# ADC2.net
KiCad netlist of a schematic drawn in Altium Designer
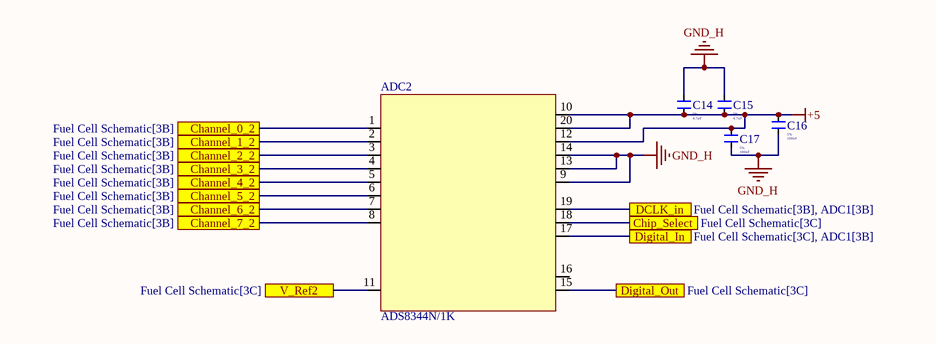
[diagram p0: ADC2.SchDoc]

(export (version "E")
  (design (tool "Eeschema 10.0.6"))
  (components
    (comp (ref "ADC2")
      (value "ADS8344N/1K")
      (footprint "ADS8344")
      (description "IC ADC 16BIT SAR 20SSOP")
      (fields (field (name "MANUFACTURER") "Texas Instruments"))
      (libsource (lib "Schlib1") (part "ADS8344N/1K"))
    )
    (comp (ref "C14")
      (value "~")
      (footprint "Capacitor_Kemet_0805")
      (description "CAP CER 4.7UF 16V X7R 0805")
      (fields
        (field (name "MANUFACTURER") "KEMET")
        (field (name "MANUFACTURER PART NUMBER") "C0805C475J4RACAUTO")
        (field (name "TOLERANCE") "5%")
        (field (name "CAPACITANCE") "4.7uF")
      )
      (libsource (lib "Schlib1") (part "C0805C475J4RACAUTO"))
    )
    (comp (ref "C15")
      (value "~")
      (footprint "Capacitor_Kemet_0805")
      (description "CAP CER 4.7UF 16V X7R 0805")
      (fields
        (field (name "MANUFACTURER") "KEMET")
        (field (name "MANUFACTURER PART NUMBER") "C0805C475J4RACAUTO")
        (field (name "TOLERANCE") "5%")
        (field (name "CAPACITANCE") "4.7uF")
      )
      (libsource (lib "Schlib1") (part "C0805C475J4RACAUTO"))
    )
    (comp (ref "C16")
      (value "~")
      (footprint "Capacitor_Kemet_0805")
      (description "Cap Ceramic 0.1uF 16V X7R 5% SMD 0805 125°C Plastic T/R")
      (fields
        (field (name "MANUFACTURER") "KEMET")
        (field (name "MANUFACTURER PART NUMBER") "C0805C104J4RACTU")
        (field (name "DISSIPATION FACTOR") "5%")
        (field (name "CAPACITANCE") "100nF")
      )
      (libsource (lib "Schlib1") (part "C0805C104J4RACTU"))
    )
    (comp (ref "C17")
      (value "~")
      (footprint "Capacitor_Kemet_0805")
      (description "Cap Ceramic 0.1uF 16V X7R 5% SMD 0805 125°C Plastic T/R")
      (fields
        (field (name "MANUFACTURER") "KEMET")
        (field (name "MANUFACTURER PART NUMBER") "C0805C104J4RACTU")
        (field (name "DISSIPATION FACTOR") "5%")
        (field (name "CAPACITANCE") "100nF")
      )
      (libsource (lib "Schlib1") (part "C0805C104J4RACTU"))
    )
  )
  (nets
    (net (code "1") (name "+5") (class "Default")
      (node (ref "ADC2") (pin "10") (pinfunction "Shutdown_10") (pintype "passive"))
      (node (ref "ADC2") (pin "12") (pinfunction "+VCC_12") (pintype "passive"))
      (node (ref "ADC2") (pin "20") (pinfunction "+VCC_20") (pintype "passive"))
      (node (ref "C14") (pin "1") (pinfunction "1_1") (pintype "passive"))
      (node (ref "C15") (pin "1") (pinfunction "1_1") (pintype "passive"))
      (node (ref "C16") (pin "2") (pinfunction "2_2") (pintype "passive"))
      (node (ref "C17") (pin "2") (pinfunction "2_2") (pintype "passive"))
    )
    (net (code "2") (name "/Channel_0_2") (class "Default")
      (node (ref "ADC2") (pin "1") (pinfunction "Channel_0_1") (pintype "passive"))
    )
    (net (code "3") (name "/Channel_1_2") (class "Default")
      (node (ref "ADC2") (pin "2") (pinfunction "Channel_1_2") (pintype "passive"))
    )
    (net (code "4") (name "/Channel_2_2") (class "Default")
      (node (ref "ADC2") (pin "3") (pinfunction "Channel_2_3") (pintype "passive"))
    )
    (net (code "5") (name "/Channel_3_2") (class "Default")
      (node (ref "ADC2") (pin "4") (pinfunction "Channel_3_4") (pintype "passive"))
    )
    (net (code "6") (name "/Channel_4_2") (class "Default")
      (node (ref "ADC2") (pin "5") (pinfunction "Channel_4_5") (pintype "passive"))
    )
    (net (code "7") (name "/Channel_5_2") (class "Default")
      (node (ref "ADC2") (pin "6") (pinfunction "Channel_5_6") (pintype "passive"))
    )
    (net (code "8") (name "/Channel_6_2") (class "Default")
      (node (ref "ADC2") (pin "7") (pinfunction "Channel_6_7") (pintype "passive"))
    )
    (net (code "9") (name "/Channel_7_2") (class "Default")
      (node (ref "ADC2") (pin "8") (pinfunction "Channel_7_8") (pintype "passive"))
    )
    (net (code "10") (name "/Chip_Select") (class "Default")
      (node (ref "ADC2") (pin "18") (pinfunction "Chip_Select_18") (pintype "passive"))
    )
    (net (code "11") (name "/DCLK_in") (class "Default")
      (node (ref "ADC2") (pin "19") (pinfunction "Digital_Clock_19") (pintype "passive"))
    )
    (net (code "12") (name "/Digital_In") (class "Default")
      (node (ref "ADC2") (pin "17") (pinfunction "Digital_In_17") (pintype "passive"))
    )
    (net (code "13") (name "/Digital_Out") (class "Default")
      (node (ref "ADC2") (pin "15") (pinfunction "Digital_Out_15") (pintype "passive"))
    )
    (net (code "14") (name "/V_Ref2") (class "Default")
      (node (ref "ADC2") (pin "11") (pinfunction "V_Reference_11") (pintype "passive"))
    )
    (net (code "15") (name "GND_H") (class "Default")
      (node (ref "ADC2") (pin "13") (pinfunction "Ground_13") (pintype "passive"))
      (node (ref "ADC2") (pin "14") (pinfunction "Ground_14") (pintype "passive"))
      (node (ref "ADC2") (pin "9") (pinfunction "Common_Reference_9") (pintype "passive"))
      (node (ref "C14") (pin "2") (pinfunction "2_2") (pintype "passive"))
      (node (ref "C15") (pin "2") (pinfunction "2_2") (pintype "passive"))
      (node (ref "C16") (pin "1") (pinfunction "1_1") (pintype "passive"))
      (node (ref "C17") (pin "1") (pinfunction "1_1") (pintype "passive"))
    )
    (net (code "16") (name "unconnected-(ADC2-Busy-Pad16)") (class "Default")
      (node (ref "ADC2") (pin "16") (pinfunction "Busy_16") (pintype "passive"))
    )
  )
)
